# Interface_DSP_FPGA.net
KiCad netlist of a schematic drawn in Altium Designer
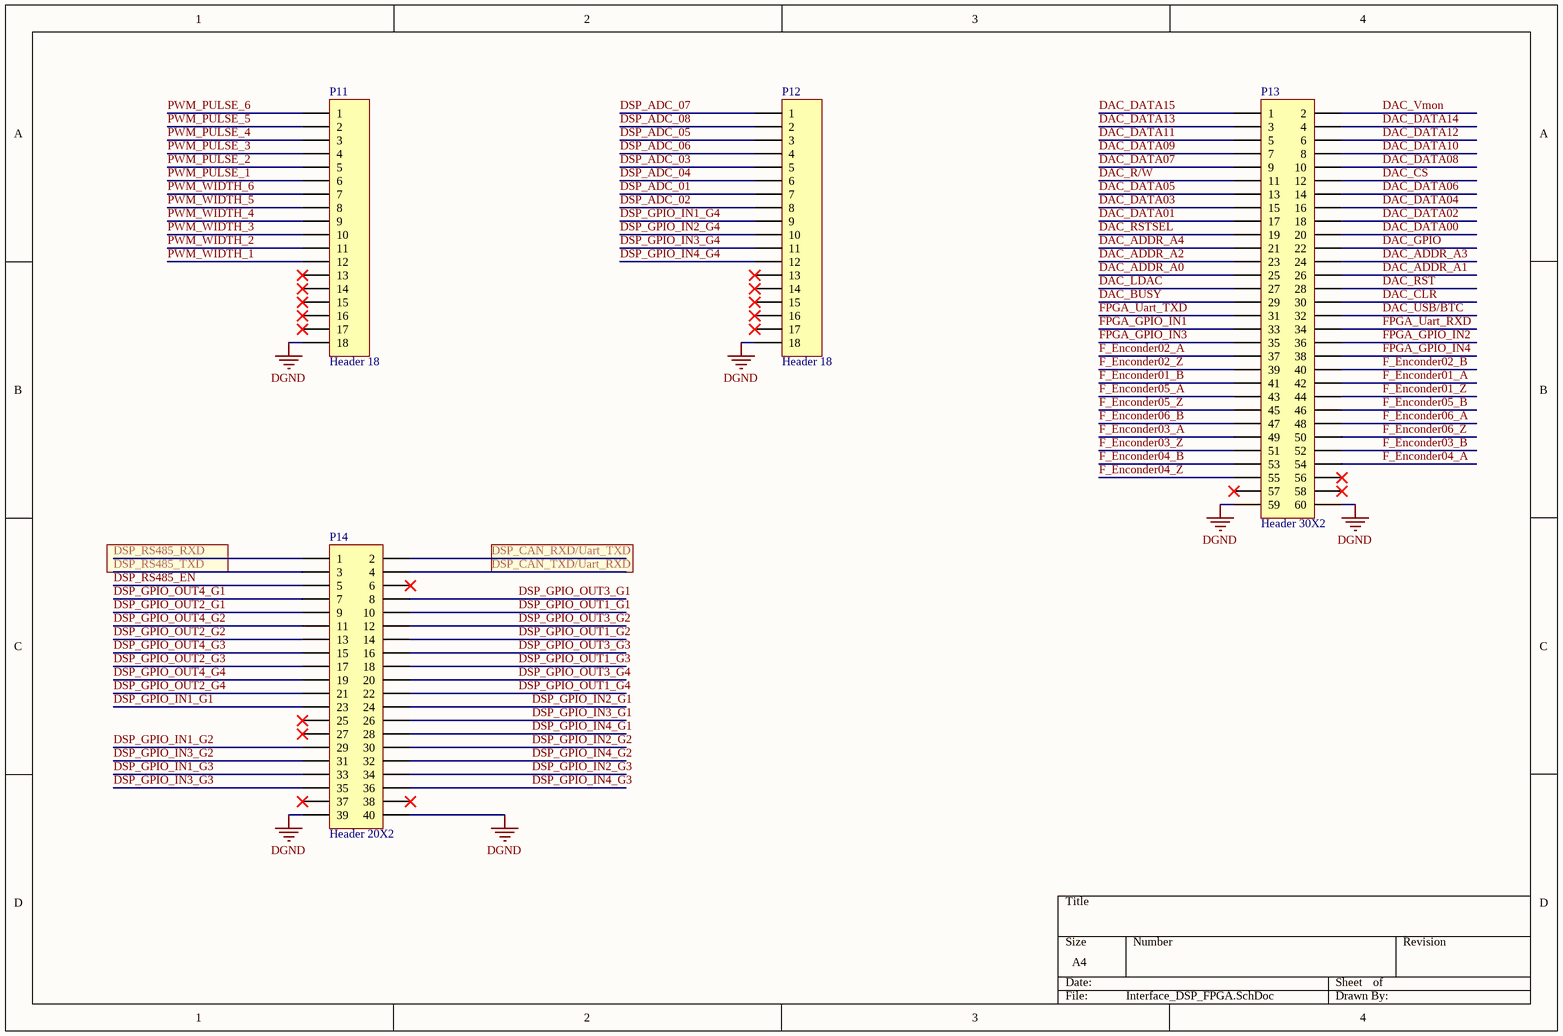
[diagram p0: Interface_DSP_FPGA.SchDoc]

(export (version "E")
  (design (tool "Eeschema 10.0.6"))
  (components
    (comp (ref "P11")
      (value "Header 18")
      (footprint "HDR1X18")
      (description "Header, 18-Pin")
      (fields (field (name "PUBLISHER") "Altium Limited"))
      (libsource (lib "Miscellaneous Connectors") (part "Header 18"))
    )
    (comp (ref "P12")
      (value "Header 18")
      (footprint "HDR1X18")
      (description "Header, 18-Pin")
      (fields (field (name "PUBLISHER") "Altium Limited"))
      (libsource (lib "Miscellaneous Connectors") (part "Header 18"))
    )
    (comp (ref "P13")
      (value "Header 30X2")
      (footprint "HDR2X30")
      (description "Header, 30-Pin, Dual row")
      (fields (field (name "PUBLISHER") "Altium Limited"))
      (libsource (lib "Miscellaneous Connectors") (part "Header 30X2"))
    )
    (comp (ref "P14")
      (value "Header 20X2")
      (footprint "HDR2X20")
      (description "Header, 20-Pin, Dual row")
      (fields (field (name "PUBLISHER") "Altium Limited"))
      (libsource (lib "Miscellaneous Connectors") (part "Header 20X2"))
    )
  )
  (nets
    (net (code "1") (name "/DAC_ADDR_A0") (class "Default")
      (node (ref "P13") (pin "25") (pinfunction "25_25") (pintype "passive"))
    )
    (net (code "2") (name "/DAC_ADDR_A1") (class "Default")
      (node (ref "P13") (pin "26") (pinfunction "26_26") (pintype "passive"))
    )
    (net (code "3") (name "/DAC_ADDR_A2") (class "Default")
      (node (ref "P13") (pin "23") (pinfunction "23_23") (pintype "passive"))
    )
    (net (code "4") (name "/DAC_ADDR_A3") (class "Default")
      (node (ref "P13") (pin "24") (pinfunction "24_24") (pintype "passive"))
    )
    (net (code "5") (name "/DAC_ADDR_A4") (class "Default")
      (node (ref "P13") (pin "21") (pinfunction "21_21") (pintype "passive"))
    )
    (net (code "6") (name "/DAC_BUSY") (class "Default")
      (node (ref "P13") (pin "29") (pinfunction "29_29") (pintype "passive"))
    )
    (net (code "7") (name "/DAC_CLR") (class "Default")
      (node (ref "P13") (pin "30") (pinfunction "30_30") (pintype "passive"))
    )
    (net (code "8") (name "/DAC_CS") (class "Default")
      (node (ref "P13") (pin "12") (pinfunction "12_12") (pintype "passive"))
    )
    (net (code "9") (name "/DAC_DATA00") (class "Default")
      (node (ref "P13") (pin "20") (pinfunction "20_20") (pintype "passive"))
    )
    (net (code "10") (name "/DAC_DATA01") (class "Default")
      (node (ref "P13") (pin "17") (pinfunction "17_17") (pintype "passive"))
    )
    (net (code "11") (name "/DAC_DATA02") (class "Default")
      (node (ref "P13") (pin "18") (pinfunction "18_18") (pintype "passive"))
    )
    (net (code "12") (name "/DAC_DATA03") (class "Default")
      (node (ref "P13") (pin "15") (pinfunction "15_15") (pintype "passive"))
    )
    (net (code "13") (name "/DAC_DATA04") (class "Default")
      (node (ref "P13") (pin "16") (pinfunction "16_16") (pintype "passive"))
    )
    (net (code "14") (name "/DAC_DATA05") (class "Default")
      (node (ref "P13") (pin "13") (pinfunction "13_13") (pintype "passive"))
    )
    (net (code "15") (name "/DAC_DATA06") (class "Default")
      (node (ref "P13") (pin "14") (pinfunction "14_14") (pintype "passive"))
    )
    (net (code "16") (name "/DAC_DATA07") (class "Default")
      (node (ref "P13") (pin "9") (pinfunction "9_9") (pintype "passive"))
    )
    (net (code "17") (name "/DAC_DATA08") (class "Default")
      (node (ref "P13") (pin "10") (pinfunction "10_10") (pintype "passive"))
    )
    (net (code "18") (name "/DAC_DATA09") (class "Default")
      (node (ref "P13") (pin "7") (pinfunction "7_7") (pintype "passive"))
    )
    (net (code "19") (name "/DAC_DATA10") (class "Default")
      (node (ref "P13") (pin "8") (pinfunction "8_8") (pintype "passive"))
    )
    (net (code "20") (name "/DAC_DATA11") (class "Default")
      (node (ref "P13") (pin "5") (pinfunction "5_5") (pintype "passive"))
    )
    (net (code "21") (name "/DAC_DATA12") (class "Default")
      (node (ref "P13") (pin "6") (pinfunction "6_6") (pintype "passive"))
    )
    (net (code "22") (name "/DAC_DATA13") (class "Default")
      (node (ref "P13") (pin "3") (pinfunction "3_3") (pintype "passive"))
    )
    (net (code "23") (name "/DAC_DATA14") (class "Default")
      (node (ref "P13") (pin "4") (pinfunction "4_4") (pintype "passive"))
    )
    (net (code "24") (name "/DAC_DATA15") (class "Default")
      (node (ref "P13") (pin "1") (pinfunction "1_1") (pintype "passive"))
    )
    (net (code "25") (name "/DAC_GPIO") (class "Default")
      (node (ref "P13") (pin "22") (pinfunction "22_22") (pintype "passive"))
    )
    (net (code "26") (name "/DAC_LDAC") (class "Default")
      (node (ref "P13") (pin "27") (pinfunction "27_27") (pintype "passive"))
    )
    (net (code "27") (name "/DAC_RST") (class "Default")
      (node (ref "P13") (pin "28") (pinfunction "28_28") (pintype "passive"))
    )
    (net (code "28") (name "/DAC_RSTSEL") (class "Default")
      (node (ref "P13") (pin "19") (pinfunction "19_19") (pintype "passive"))
    )
    (net (code "29") (name "/DAC_R{slash}W") (class "Default")
      (node (ref "P13") (pin "11") (pinfunction "11_11") (pintype "passive"))
    )
    (net (code "30") (name "/DAC_USB{slash}BTC") (class "Default")
      (node (ref "P13") (pin "32") (pinfunction "32_32") (pintype "passive"))
    )
    (net (code "31") (name "/DAC_Vmon") (class "Default")
      (node (ref "P13") (pin "2") (pinfunction "2_2") (pintype "passive"))
    )
    (net (code "32") (name "/DSP_ADC_01") (class "Default")
      (node (ref "P12") (pin "7") (pinfunction "7_7") (pintype "passive"))
    )
    (net (code "33") (name "/DSP_ADC_02") (class "Default")
      (node (ref "P12") (pin "8") (pinfunction "8_8") (pintype "passive"))
    )
    (net (code "34") (name "/DSP_ADC_03") (class "Default")
      (node (ref "P12") (pin "5") (pinfunction "5_5") (pintype "passive"))
    )
    (net (code "35") (name "/DSP_ADC_04") (class "Default")
      (node (ref "P12") (pin "6") (pinfunction "6_6") (pintype "passive"))
    )
    (net (code "36") (name "/DSP_ADC_05") (class "Default")
      (node (ref "P12") (pin "3") (pinfunction "3_3") (pintype "passive"))
    )
    (net (code "37") (name "/DSP_ADC_06") (class "Default")
      (node (ref "P12") (pin "4") (pinfunction "4_4") (pintype "passive"))
    )
    (net (code "38") (name "/DSP_ADC_07") (class "Default")
      (node (ref "P12") (pin "1") (pinfunction "1_1") (pintype "passive"))
    )
    (net (code "39") (name "/DSP_ADC_08") (class "Default")
      (node (ref "P12") (pin "2") (pinfunction "2_2") (pintype "passive"))
    )
    (net (code "40") (name "/DSP_CAN_RXD{slash}Uart_TXD") (class "Default")
      (node (ref "P14") (pin "2") (pinfunction "2_2") (pintype "passive"))
    )
    (net (code "41") (name "/DSP_CAN_TXD{slash}Uart_RXD") (class "Default")
      (node (ref "P14") (pin "4") (pinfunction "4_4") (pintype "passive"))
    )
    (net (code "42") (name "/DSP_GPIO_IN1_G1") (class "Default")
      (node (ref "P14") (pin "23") (pinfunction "23_23") (pintype "passive"))
    )
    (net (code "43") (name "/DSP_GPIO_IN1_G2") (class "Default")
      (node (ref "P14") (pin "29") (pinfunction "29_29") (pintype "passive"))
    )
    (net (code "44") (name "/DSP_GPIO_IN1_G3") (class "Default")
      (node (ref "P14") (pin "33") (pinfunction "33_33") (pintype "passive"))
    )
    (net (code "45") (name "/DSP_GPIO_IN1_G4") (class "Default")
      (node (ref "P12") (pin "9") (pinfunction "9_9") (pintype "passive"))
    )
    (net (code "46") (name "/DSP_GPIO_IN2_G1") (class "Default")
      (node (ref "P14") (pin "24") (pinfunction "24_24") (pintype "passive"))
    )
    (net (code "47") (name "/DSP_GPIO_IN2_G2") (class "Default")
      (node (ref "P14") (pin "30") (pinfunction "30_30") (pintype "passive"))
    )
    (net (code "48") (name "/DSP_GPIO_IN2_G3") (class "Default")
      (node (ref "P14") (pin "34") (pinfunction "34_34") (pintype "passive"))
    )
    (net (code "49") (name "/DSP_GPIO_IN2_G4") (class "Default")
      (node (ref "P12") (pin "10") (pinfunction "10_10") (pintype "passive"))
    )
    (net (code "50") (name "/DSP_GPIO_IN3_G1") (class "Default")
      (node (ref "P14") (pin "26") (pinfunction "26_26") (pintype "passive"))
    )
    (net (code "51") (name "/DSP_GPIO_IN3_G2") (class "Default")
      (node (ref "P14") (pin "31") (pinfunction "31_31") (pintype "passive"))
    )
    (net (code "52") (name "/DSP_GPIO_IN3_G3") (class "Default")
      (node (ref "P14") (pin "35") (pinfunction "35_35") (pintype "passive"))
    )
    (net (code "53") (name "/DSP_GPIO_IN3_G4") (class "Default")
      (node (ref "P12") (pin "11") (pinfunction "11_11") (pintype "passive"))
    )
    (net (code "54") (name "/DSP_GPIO_IN4_G1") (class "Default")
      (node (ref "P14") (pin "28") (pinfunction "28_28") (pintype "passive"))
    )
    (net (code "55") (name "/DSP_GPIO_IN4_G2") (class "Default")
      (node (ref "P14") (pin "32") (pinfunction "32_32") (pintype "passive"))
    )
    (net (code "56") (name "/DSP_GPIO_IN4_G3") (class "Default")
      (node (ref "P14") (pin "36") (pinfunction "36_36") (pintype "passive"))
    )
    (net (code "57") (name "/DSP_GPIO_IN4_G4") (class "Default")
      (node (ref "P12") (pin "12") (pinfunction "12_12") (pintype "passive"))
    )
    (net (code "58") (name "/DSP_GPIO_OUT1_G1") (class "Default")
      (node (ref "P14") (pin "10") (pinfunction "10_10") (pintype "passive"))
    )
    (net (code "59") (name "/DSP_GPIO_OUT1_G2") (class "Default")
      (node (ref "P14") (pin "14") (pinfunction "14_14") (pintype "passive"))
    )
    (net (code "60") (name "/DSP_GPIO_OUT1_G3") (class "Default")
      (node (ref "P14") (pin "18") (pinfunction "18_18") (pintype "passive"))
    )
    (net (code "61") (name "/DSP_GPIO_OUT1_G4") (class "Default")
      (node (ref "P14") (pin "22") (pinfunction "22_22") (pintype "passive"))
    )
    (net (code "62") (name "/DSP_GPIO_OUT2_G1") (class "Default")
      (node (ref "P14") (pin "9") (pinfunction "9_9") (pintype "passive"))
    )
    (net (code "63") (name "/DSP_GPIO_OUT2_G2") (class "Default")
      (node (ref "P14") (pin "13") (pinfunction "13_13") (pintype "passive"))
    )
    (net (code "64") (name "/DSP_GPIO_OUT2_G3") (class "Default")
      (node (ref "P14") (pin "17") (pinfunction "17_17") (pintype "passive"))
    )
    (net (code "65") (name "/DSP_GPIO_OUT2_G4") (class "Default")
      (node (ref "P14") (pin "21") (pinfunction "21_21") (pintype "passive"))
    )
    (net (code "66") (name "/DSP_GPIO_OUT3_G1") (class "Default")
      (node (ref "P14") (pin "8") (pinfunction "8_8") (pintype "passive"))
    )
    (net (code "67") (name "/DSP_GPIO_OUT3_G2") (class "Default")
      (node (ref "P14") (pin "12") (pinfunction "12_12") (pintype "passive"))
    )
    (net (code "68") (name "/DSP_GPIO_OUT3_G3") (class "Default")
      (node (ref "P14") (pin "16") (pinfunction "16_16") (pintype "passive"))
    )
    (net (code "69") (name "/DSP_GPIO_OUT3_G4") (class "Default")
      (node (ref "P14") (pin "20") (pinfunction "20_20") (pintype "passive"))
    )
    (net (code "70") (name "/DSP_GPIO_OUT4_G1") (class "Default")
      (node (ref "P14") (pin "7") (pinfunction "7_7") (pintype "passive"))
    )
    (net (code "71") (name "/DSP_GPIO_OUT4_G2") (class "Default")
      (node (ref "P14") (pin "11") (pinfunction "11_11") (pintype "passive"))
    )
    (net (code "72") (name "/DSP_GPIO_OUT4_G3") (class "Default")
      (node (ref "P14") (pin "15") (pinfunction "15_15") (pintype "passive"))
    )
    (net (code "73") (name "/DSP_GPIO_OUT4_G4") (class "Default")
      (node (ref "P14") (pin "19") (pinfunction "19_19") (pintype "passive"))
    )
    (net (code "74") (name "/DSP_RS485_EN") (class "Default")
      (node (ref "P14") (pin "5") (pinfunction "5_5") (pintype "passive"))
    )
    (net (code "75") (name "/DSP_RS485_RXD") (class "Default")
      (node (ref "P14") (pin "1") (pinfunction "1_1") (pintype "passive"))
    )
    (net (code "76") (name "/DSP_RS485_TXD") (class "Default")
      (node (ref "P14") (pin "3") (pinfunction "3_3") (pintype "passive"))
    )
    (net (code "77") (name "/FPGA_GPIO_IN1") (class "Default")
      (node (ref "P13") (pin "33") (pinfunction "33_33") (pintype "passive"))
    )
    (net (code "78") (name "/FPGA_GPIO_IN2") (class "Default")
      (node (ref "P13") (pin "36") (pinfunction "36_36") (pintype "passive"))
    )
    (net (code "79") (name "/FPGA_GPIO_IN3") (class "Default")
      (node (ref "P13") (pin "35") (pinfunction "35_35") (pintype "passive"))
    )
    (net (code "80") (name "/FPGA_GPIO_IN4") (class "Default")
      (node (ref "P13") (pin "38") (pinfunction "38_38") (pintype "passive"))
    )
    (net (code "81") (name "/FPGA_Uart_RXD") (class "Default")
      (node (ref "P13") (pin "34") (pinfunction "34_34") (pintype "passive"))
    )
    (net (code "82") (name "/FPGA_Uart_TXD") (class "Default")
      (node (ref "P13") (pin "31") (pinfunction "31_31") (pintype "passive"))
    )
    (net (code "83") (name "/F_Enconder01_A") (class "Default")
      (node (ref "P13") (pin "42") (pinfunction "42_42") (pintype "passive"))
    )
    (net (code "84") (name "/F_Enconder01_B") (class "Default")
      (node (ref "P13") (pin "41") (pinfunction "41_41") (pintype "passive"))
    )
    (net (code "85") (name "/F_Enconder01_Z") (class "Default")
      (node (ref "P13") (pin "44") (pinfunction "44_44") (pintype "passive"))
    )
    (net (code "86") (name "/F_Enconder02_A") (class "Default")
      (node (ref "P13") (pin "37") (pinfunction "37_37") (pintype "passive"))
    )
    (net (code "87") (name "/F_Enconder02_B") (class "Default")
      (node (ref "P13") (pin "40") (pinfunction "40_40") (pintype "passive"))
    )
    (net (code "88") (name "/F_Enconder02_Z") (class "Default")
      (node (ref "P13") (pin "39") (pinfunction "39_39") (pintype "passive"))
    )
    (net (code "89") (name "/F_Enconder03_A") (class "Default")
      (node (ref "P13") (pin "49") (pinfunction "49_49") (pintype "passive"))
    )
    (net (code "90") (name "/F_Enconder03_B") (class "Default")
      (node (ref "P13") (pin "52") (pinfunction "52_52") (pintype "passive"))
    )
    (net (code "91") (name "/F_Enconder03_Z") (class "Default")
      (node (ref "P13") (pin "51") (pinfunction "51_51") (pintype "passive"))
    )
    (net (code "92") (name "/F_Enconder04_A") (class "Default")
      (node (ref "P13") (pin "54") (pinfunction "54_54") (pintype "passive"))
    )
    (net (code "93") (name "/F_Enconder04_B") (class "Default")
      (node (ref "P13") (pin "53") (pinfunction "53_53") (pintype "passive"))
    )
    (net (code "94") (name "/F_Enconder04_Z") (class "Default")
      (node (ref "P13") (pin "55") (pinfunction "55_55") (pintype "passive"))
    )
    (net (code "95") (name "/F_Enconder05_A") (class "Default")
      (node (ref "P13") (pin "43") (pinfunction "43_43") (pintype "passive"))
    )
    (net (code "96") (name "/F_Enconder05_B") (class "Default")
      (node (ref "P13") (pin "46") (pinfunction "46_46") (pintype "passive"))
    )
    (net (code "97") (name "/F_Enconder05_Z") (class "Default")
      (node (ref "P13") (pin "45") (pinfunction "45_45") (pintype "passive"))
    )
    (net (code "98") (name "/F_Enconder06_A") (class "Default")
      (node (ref "P13") (pin "48") (pinfunction "48_48") (pintype "passive"))
    )
    (net (code "99") (name "/F_Enconder06_B") (class "Default")
      (node (ref "P13") (pin "47") (pinfunction "47_47") (pintype "passive"))
    )
    (net (code "100") (name "/F_Enconder06_Z") (class "Default")
      (node (ref "P13") (pin "50") (pinfunction "50_50") (pintype "passive"))
    )
    (net (code "101") (name "/PWM_PULSE_1") (class "Default")
      (node (ref "P11") (pin "6") (pinfunction "6_6") (pintype "passive"))
    )
    (net (code "102") (name "/PWM_PULSE_2") (class "Default")
      (node (ref "P11") (pin "5") (pinfunction "5_5") (pintype "passive"))
    )
    (net (code "103") (name "/PWM_PULSE_3") (class "Default")
      (node (ref "P11") (pin "4") (pinfunction "4_4") (pintype "passive"))
    )
    (net (code "104") (name "/PWM_PULSE_4") (class "Default")
      (node (ref "P11") (pin "3") (pinfunction "3_3") (pintype "passive"))
    )
    (net (code "105") (name "/PWM_PULSE_5") (class "Default")
      (node (ref "P11") (pin "2") (pinfunction "2_2") (pintype "passive"))
    )
    (net (code "106") (name "/PWM_PULSE_6") (class "Default")
      (node (ref "P11") (pin "1") (pinfunction "1_1") (pintype "passive"))
    )
    (net (code "107") (name "/PWM_WIDTH_1") (class "Default")
      (node (ref "P11") (pin "12") (pinfunction "12_12") (pintype "passive"))
    )
    (net (code "108") (name "/PWM_WIDTH_2") (class "Default")
      (node (ref "P11") (pin "11") (pinfunction "11_11") (pintype "passive"))
    )
    (net (code "109") (name "/PWM_WIDTH_3") (class "Default")
      (node (ref "P11") (pin "10") (pinfunction "10_10") (pintype "passive"))
    )
    (net (code "110") (name "/PWM_WIDTH_4") (class "Default")
      (node (ref "P11") (pin "9") (pinfunction "9_9") (pintype "passive"))
    )
    (net (code "111") (name "/PWM_WIDTH_5") (class "Default")
      (node (ref "P11") (pin "8") (pinfunction "8_8") (pintype "passive"))
    )
    (net (code "112") (name "/PWM_WIDTH_6") (class "Default")
      (node (ref "P11") (pin "7") (pinfunction "7_7") (pintype "passive"))
    )
    (net (code "113") (name "DGND") (class "Default")
      (node (ref "P11") (pin "18") (pinfunction "18_18") (pintype "passive"))
      (node (ref "P12") (pin "18") (pinfunction "18_18") (pintype "passive"))
      (node (ref "P13") (pin "59") (pinfunction "59_59") (pintype "passive"))
      (node (ref "P13") (pin "60") (pinfunction "60_60") (pintype "passive"))
      (node (ref "P14") (pin "39") (pinfunction "39_39") (pintype "passive"))
      (node (ref "P14") (pin "40") (pinfunction "40_40") (pintype "passive"))
    )
    (net (code "114") (name "unconnected-(P11-Pad13)") (class "Default")
      (node (ref "P11") (pin "13") (pinfunction "13_13") (pintype "passive+no_connect"))
    )
    (net (code "115") (name "unconnected-(P11-Pad14)") (class "Default")
      (node (ref "P11") (pin "14") (pinfunction "14_14") (pintype "passive+no_connect"))
    )
    (net (code "116") (name "unconnected-(P11-Pad15)") (class "Default")
      (node (ref "P11") (pin "15") (pinfunction "15_15") (pintype "passive+no_connect"))
    )
    (net (code "117") (name "unconnected-(P11-Pad16)") (class "Default")
      (node (ref "P11") (pin "16") (pinfunction "16_16") (pintype "passive+no_connect"))
    )
    (net (code "118") (name "unconnected-(P11-Pad17)") (class "Default")
      (node (ref "P11") (pin "17") (pinfunction "17_17") (pintype "passive+no_connect"))
    )
    (net (code "119") (name "unconnected-(P12-Pad13)") (class "Default")
      (node (ref "P12") (pin "13") (pinfunction "13_13") (pintype "passive+no_connect"))
    )
    (net (code "120") (name "unconnected-(P12-Pad14)") (class "Default")
      (node (ref "P12") (pin "14") (pinfunction "14_14") (pintype "passive+no_connect"))
    )
    (net (code "121") (name "unconnected-(P12-Pad15)") (class "Default")
      (node (ref "P12") (pin "15") (pinfunction "15_15") (pintype "passive+no_connect"))
    )
    (net (code "122") (name "unconnected-(P12-Pad16)") (class "Default")
      (node (ref "P12") (pin "16") (pinfunction "16_16") (pintype "passive+no_connect"))
    )
    (net (code "123") (name "unconnected-(P12-Pad17)") (class "Default")
      (node (ref "P12") (pin "17") (pinfunction "17_17") (pintype "passive+no_connect"))
    )
    (net (code "124") (name "unconnected-(P13-Pad56)") (class "Default")
      (node (ref "P13") (pin "56") (pinfunction "56_56") (pintype "passive+no_connect"))
    )
    (net (code "125") (name "unconnected-(P13-Pad57)") (class "Default")
      (node (ref "P13") (pin "57") (pinfunction "57_57") (pintype "passive+no_connect"))
    )
    (net (code "126") (name "unconnected-(P13-Pad58)") (class "Default")
      (node (ref "P13") (pin "58") (pinfunction "58_58") (pintype "passive+no_connect"))
    )
    (net (code "127") (name "unconnected-(P14-Pad6)") (class "Default")
      (node (ref "P14") (pin "6") (pinfunction "6_6") (pintype "passive+no_connect"))
    )
    (net (code "128") (name "unconnected-(P14-Pad25)") (class "Default")
      (node (ref "P14") (pin "25") (pinfunction "25_25") (pintype "passive+no_connect"))
    )
    (net (code "129") (name "unconnected-(P14-Pad27)") (class "Default")
      (node (ref "P14") (pin "27") (pinfunction "27_27") (pintype "passive+no_connect"))
    )
    (net (code "130") (name "unconnected-(P14-Pad37)") (class "Default")
      (node (ref "P14") (pin "37") (pinfunction "37_37") (pintype "passive+no_connect"))
    )
    (net (code "131") (name "unconnected-(P14-Pad38)") (class "Default")
      (node (ref "P14") (pin "38") (pinfunction "38_38") (pintype "passive+no_connect"))
    )
  )
)
